# CRUVI.net
KiCad netlist of a schematic drawn in Altium Designer
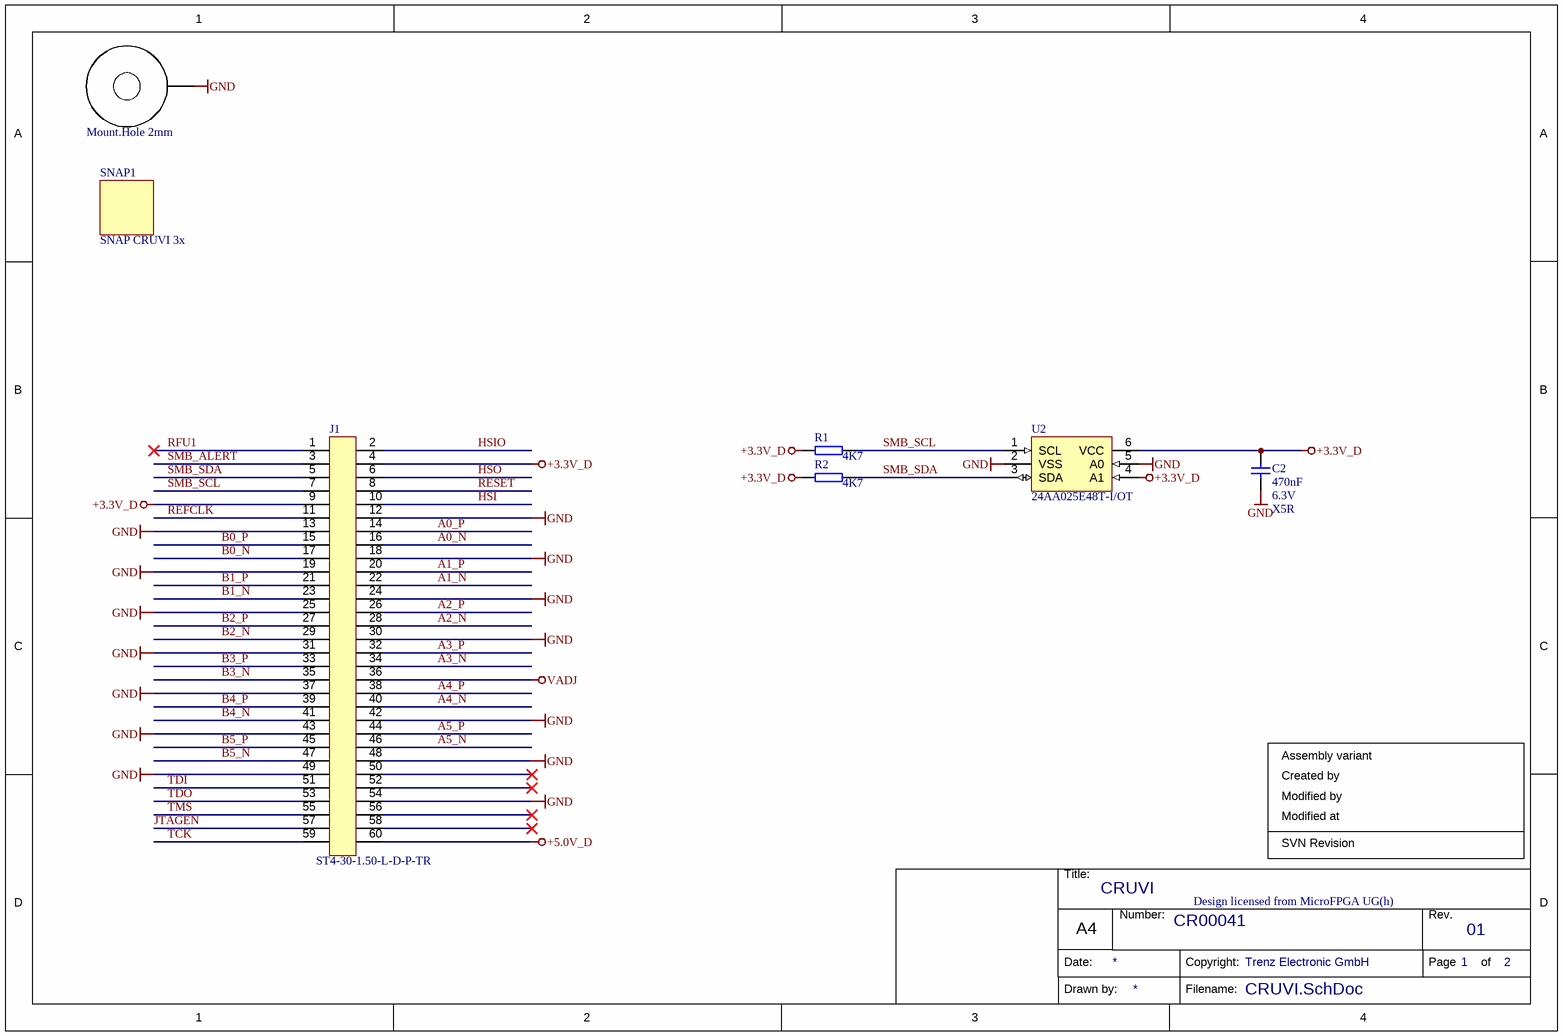
[diagram p0: CRUVI.SchDoc]

(export (version "E")
  (design (tool "Eeschema 10.0.6"))
  (components
    (comp (ref "C2")
      (value "470nF")
      (footprint "CAPC1005X55N")
      (description "KON 470nF 6,3V X5R SMD BF 1005 (0402)")
      (fields (field (name "VOLTAGE") "6.3V") (field (name "TECHNOLOGY") "X5R"))
      (libsource (lib "TE") (part "CAP-NP"))
    )
    (comp (ref "H1") (value "Mount.Hole 2mm") (footprint "MHole2_2mm") (libsource (lib "TE") (part "MHole")))
    (comp (ref "J1")
      (value "ST4-30-1.50-L-D-P-TR")
      (footprint "ST4-30-1_50-L-D")
      (libsource (lib "TE") (part "CON-60"))
    )
    (comp (ref "R1")
      (value "4K7")
      (footprint "RESC1005X40N")
      (description "WID SMD 4K7 1% 0,063W BF 1005 (0402)")
      (fields (field (name "TOLERANCE") "1%"))
      (libsource (lib "TE") (part "RES"))
    )
    (comp (ref "R2")
      (value "4K7")
      (footprint "RESC1005X40N")
      (description "WID SMD 4K7 1% 0,063W BF 1005 (0402)")
      (fields (field (name "TOLERANCE") "1%"))
      (libsource (lib "TE") (part "RES"))
    )
    (comp (ref "SNAP1")
      (value "SNAP CRUVI 3x")
      (footprint "CRUVI_3x_Snap")
      (description "SNAP for CRUVI 3x")
      (libsource (lib "TE") (part "DUMMY"))
    )
    (comp (ref "U2")
      (value "24AA025E48T-I/OT")
      (footprint "SOT95P280X145-6N")
      (libsource (lib "TE") (part "24AA025E48"))
    )
  )
  (nets
    (net (code "1") (name "+3.3V_D") (class "Default")
      (node (ref "C2") (pin "1") (pinfunction "1_1") (pintype "passive"))
      (node (ref "J1") (pin "4") (pinfunction "4_4") (pintype "passive"))
      (node (ref "J1") (pin "9") (pinfunction "9_9") (pintype "passive"))
      (node (ref "R1") (pin "1") (pinfunction "1_1") (pintype "passive"))
      (node (ref "R2") (pin "1") (pinfunction "1_1") (pintype "passive"))
      (node (ref "U2") (pin "4") (pinfunction "A1_4") (pintype "input"))
      (node (ref "U2") (pin "6") (pinfunction "VCC_6") (pintype "power_in"))
    )
    (net (code "2") (name "+5.0V_D") (class "Default")
      (node (ref "J1") (pin "60") (pinfunction "60_60") (pintype "passive"))
    )
    (net (code "3") (name "/A0_N") (class "Default")
      (node (ref "J1") (pin "16") (pinfunction "16_16") (pintype "passive"))
    )
    (net (code "4") (name "/A0_P") (class "Default")
      (node (ref "J1") (pin "14") (pinfunction "14_14") (pintype "passive"))
    )
    (net (code "5") (name "/A1_N") (class "Default")
      (node (ref "J1") (pin "22") (pinfunction "22_22") (pintype "passive"))
    )
    (net (code "6") (name "/A1_P") (class "Default")
      (node (ref "J1") (pin "20") (pinfunction "20_20") (pintype "passive"))
    )
    (net (code "7") (name "/A2_N") (class "Default")
      (node (ref "J1") (pin "28") (pinfunction "28_28") (pintype "passive"))
    )
    (net (code "8") (name "/A2_P") (class "Default")
      (node (ref "J1") (pin "26") (pinfunction "26_26") (pintype "passive"))
    )
    (net (code "9") (name "/A3_N") (class "Default")
      (node (ref "J1") (pin "34") (pinfunction "34_34") (pintype "passive"))
    )
    (net (code "10") (name "/A3_P") (class "Default")
      (node (ref "J1") (pin "32") (pinfunction "32_32") (pintype "passive"))
    )
    (net (code "11") (name "/A4_N") (class "Default")
      (node (ref "J1") (pin "40") (pinfunction "40_40") (pintype "passive"))
    )
    (net (code "12") (name "/A4_P") (class "Default")
      (node (ref "J1") (pin "38") (pinfunction "38_38") (pintype "passive"))
    )
    (net (code "13") (name "/A5_N") (class "Default")
      (node (ref "J1") (pin "46") (pinfunction "46_46") (pintype "passive"))
    )
    (net (code "14") (name "/A5_P") (class "Default")
      (node (ref "J1") (pin "44") (pinfunction "44_44") (pintype "passive"))
    )
    (net (code "15") (name "/B0_N") (class "Default")
      (node (ref "J1") (pin "17") (pinfunction "17_17") (pintype "passive"))
    )
    (net (code "16") (name "/B0_P") (class "Default")
      (node (ref "J1") (pin "15") (pinfunction "15_15") (pintype "passive"))
    )
    (net (code "17") (name "/B1_N") (class "Default")
      (node (ref "J1") (pin "23") (pinfunction "23_23") (pintype "passive"))
    )
    (net (code "18") (name "/B1_P") (class "Default")
      (node (ref "J1") (pin "21") (pinfunction "21_21") (pintype "passive"))
    )
    (net (code "19") (name "/B2_N") (class "Default")
      (node (ref "J1") (pin "29") (pinfunction "29_29") (pintype "passive"))
    )
    (net (code "20") (name "/B2_P") (class "Default")
      (node (ref "J1") (pin "27") (pinfunction "27_27") (pintype "passive"))
    )
    (net (code "21") (name "/B3_N") (class "Default")
      (node (ref "J1") (pin "35") (pinfunction "35_35") (pintype "passive"))
    )
    (net (code "22") (name "/B3_P") (class "Default")
      (node (ref "J1") (pin "33") (pinfunction "33_33") (pintype "passive"))
    )
    (net (code "23") (name "/B4_N") (class "Default")
      (node (ref "J1") (pin "41") (pinfunction "41_41") (pintype "passive"))
    )
    (net (code "24") (name "/B4_P") (class "Default")
      (node (ref "J1") (pin "39") (pinfunction "39_39") (pintype "passive"))
    )
    (net (code "25") (name "/B5_N") (class "Default")
      (node (ref "J1") (pin "47") (pinfunction "47_47") (pintype "passive"))
    )
    (net (code "26") (name "/B5_P") (class "Default")
      (node (ref "J1") (pin "45") (pinfunction "45_45") (pintype "passive"))
    )
    (net (code "27") (name "/HSI") (class "Default")
      (node (ref "J1") (pin "10") (pinfunction "10_10") (pintype "passive"))
    )
    (net (code "28") (name "/HSIO") (class "Default")
      (node (ref "J1") (pin "2") (pinfunction "2_2") (pintype "passive"))
    )
    (net (code "29") (name "/HSO") (class "Default")
      (node (ref "J1") (pin "6") (pinfunction "6_6") (pintype "passive"))
    )
    (net (code "30") (name "/JTAGEN") (class "Default")
      (node (ref "J1") (pin "57") (pinfunction "57_57") (pintype "passive"))
    )
    (net (code "31") (name "/REFCLK") (class "Default")
      (node (ref "J1") (pin "11") (pinfunction "11_11") (pintype "passive"))
    )
    (net (code "32") (name "/RESET") (class "Default")
      (node (ref "J1") (pin "8") (pinfunction "8_8") (pintype "passive"))
    )
    (net (code "33") (name "/RFU1") (class "Default")
      (node (ref "J1") (pin "1") (pinfunction "1_1") (pintype "passive+no_connect"))
    )
    (net (code "34") (name "/SMB_ALERT") (class "Default")
      (node (ref "J1") (pin "3") (pinfunction "3_3") (pintype "passive"))
    )
    (net (code "35") (name "/SMB_SCL") (class "Default")
      (node (ref "J1") (pin "7") (pinfunction "7_7") (pintype "passive"))
      (node (ref "R1") (pin "2") (pinfunction "2_2") (pintype "passive"))
      (node (ref "U2") (pin "1") (pinfunction "SCL_1") (pintype "input"))
    )
    (net (code "36") (name "/SMB_SDA") (class "Default")
      (node (ref "J1") (pin "5") (pinfunction "5_5") (pintype "passive"))
      (node (ref "R2") (pin "2") (pinfunction "2_2") (pintype "passive"))
      (node (ref "U2") (pin "3") (pinfunction "SDA_3") (pintype "bidirectional"))
    )
    (net (code "37") (name "/TCK") (class "Default")
      (node (ref "J1") (pin "59") (pinfunction "59_59") (pintype "passive"))
    )
    (net (code "38") (name "/TDI") (class "Default")
      (node (ref "J1") (pin "51") (pinfunction "51_51") (pintype "passive"))
    )
    (net (code "39") (name "/TDO") (class "Default")
      (node (ref "J1") (pin "53") (pinfunction "53_53") (pintype "passive"))
    )
    (net (code "40") (name "/TMS") (class "Default")
      (node (ref "J1") (pin "55") (pinfunction "55_55") (pintype "passive"))
    )
    (net (code "41") (name "GND") (class "Default")
      (node (ref "C2") (pin "2") (pinfunction "2_2") (pintype "passive"))
      (node (ref "H1") (pin "1") (pinfunction "1_1") (pintype "passive"))
      (node (ref "J1") (pin "12") (pinfunction "12_12") (pintype "passive"))
      (node (ref "J1") (pin "13") (pinfunction "13_13") (pintype "passive"))
      (node (ref "J1") (pin "18") (pinfunction "18_18") (pintype "passive"))
      (node (ref "J1") (pin "19") (pinfunction "19_19") (pintype "passive"))
      (node (ref "J1") (pin "24") (pinfunction "24_24") (pintype "passive"))
      (node (ref "J1") (pin "25") (pinfunction "25_25") (pintype "passive"))
      (node (ref "J1") (pin "30") (pinfunction "30_30") (pintype "passive"))
      (node (ref "J1") (pin "31") (pinfunction "31_31") (pintype "passive"))
      (node (ref "J1") (pin "37") (pinfunction "37_37") (pintype "passive"))
      (node (ref "J1") (pin "42") (pinfunction "42_42") (pintype "passive"))
      (node (ref "J1") (pin "43") (pinfunction "43_43") (pintype "passive"))
      (node (ref "J1") (pin "48") (pinfunction "48_48") (pintype "passive"))
      (node (ref "J1") (pin "49") (pinfunction "49_49") (pintype "passive"))
      (node (ref "J1") (pin "54") (pinfunction "54_54") (pintype "passive"))
      (node (ref "U2") (pin "2") (pinfunction "VSS_2") (pintype "power_in"))
      (node (ref "U2") (pin "5") (pinfunction "A0_5") (pintype "input"))
    )
    (net (code "42") (name "VADJ") (class "Default")
      (node (ref "J1") (pin "36") (pinfunction "36_36") (pintype "passive"))
    )
    (net (code "43") (name "unconnected-(J1-Pad50)") (class "Default")
      (node (ref "J1") (pin "50") (pinfunction "50_50") (pintype "passive+no_connect"))
    )
    (net (code "44") (name "unconnected-(J1-Pad52)") (class "Default")
      (node (ref "J1") (pin "52") (pinfunction "52_52") (pintype "passive+no_connect"))
    )
    (net (code "45") (name "unconnected-(J1-Pad56)") (class "Default")
      (node (ref "J1") (pin "56") (pinfunction "56_56") (pintype "passive+no_connect"))
    )
    (net (code "46") (name "unconnected-(J1-Pad58)") (class "Default")
      (node (ref "J1") (pin "58") (pinfunction "58_58") (pintype "passive+no_connect"))
    )
  )
)
